# Sheet1.net
KiCad netlist of a schematic drawn in Altium Designer
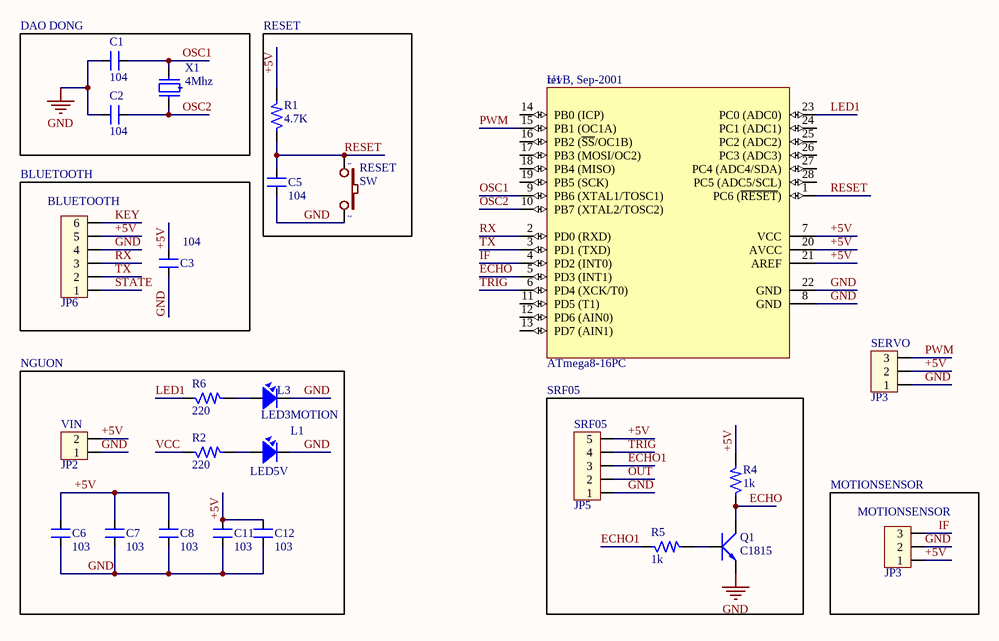
[diagram p0: Sheet1.SchDoc]

(export (version "E")
  (design (tool "Eeschema 10.0.6"))
  (components
    (comp (ref "BLUETOOTH")
      (value "JP6")
      (footprint "CON6")
      (description "Connector 6")
      (libsource (lib "syhaunguyen") (part "Con6"))
    )
    (comp (ref "C1")
      (value "104")
      (footprint "SM-0805")
      (description "Cap SMD")
      (libsource (lib "syhaunguyen") (part "CM"))
    )
    (comp (ref "C2")
      (value "104")
      (footprint "SM-0805")
      (description "Cap SMD")
      (libsource (lib "syhaunguyen") (part "CM"))
    )
    (comp (ref "C3")
      (value "104")
      (footprint "SM-0805")
      (description "Cap SMD")
      (libsource (lib "syhaunguyen") (part "CM"))
    )
    (comp (ref "C5")
      (value "104")
      (footprint "SM-0805")
      (description "Cap SMD")
      (libsource (lib "syhaunguyen") (part "CM"))
    )
    (comp (ref "C6")
      (value "103")
      (footprint "SM-0805")
      (description "Cap SMD")
      (libsource (lib "syhaunguyen") (part "CM"))
    )
    (comp (ref "C7")
      (value "103")
      (footprint "SM-0805")
      (description "Cap SMD")
      (libsource (lib "syhaunguyen") (part "CM"))
    )
    (comp (ref "C8")
      (value "103")
      (footprint "SM-0805")
      (description "Cap SMD")
      (libsource (lib "syhaunguyen") (part "CM"))
    )
    (comp (ref "C11")
      (value "103")
      (footprint "SM-0805")
      (description "Cap SMD")
      (libsource (lib "syhaunguyen") (part "CM"))
    )
    (comp (ref "C12")
      (value "103")
      (footprint "SM-0805")
      (description "Cap SMD")
      (libsource (lib "syhaunguyen") (part "CM"))
    )
    (comp (ref "L1")
      (value "LED5V")
      (footprint "LED-3")
      (description "LED Single colour Green and Red")
      (libsource (lib "syhaunguyen") (part "LED"))
    )
    (comp (ref "L3")
      (value "LED3MOTION")
      (footprint "LED-3")
      (description "LED Single colour Green and Red")
      (libsource (lib "syhaunguyen") (part "LED"))
    )
    (comp (ref "MOTIONSENSOR")
      (value "JP3")
      (footprint "CON3")
      (description "Connector 3")
      (libsource (lib "syhaunguyen") (part "Con3"))
    )
    (comp (ref "Q1")
      (value "C1815")
      (footprint "QTO-92")
      (description "NPN 600mW, ECB")
      (libsource (lib "syhaunguyen") (part "C1815"))
    )
    (comp (ref "R1")
      (value "4.7K")
      (footprint "SM-0805")
      (description "Resistor 1/4W")
      (libsource (lib "syhaunguyen") (part "R"))
    )
    (comp (ref "R2")
      (value "220")
      (footprint "SM-0805")
      (description "Resistor 1/4W")
      (libsource (lib "syhaunguyen") (part "R"))
    )
    (comp (ref "R4")
      (value "1k")
      (footprint "SM-0805")
      (description "Resistor 1/4W")
      (libsource (lib "syhaunguyen") (part "R"))
    )
    (comp (ref "R5")
      (value "1k")
      (footprint "SM-0805")
      (description "Resistor 1/4W")
      (libsource (lib "syhaunguyen") (part "R"))
    )
    (comp (ref "R6")
      (value "220")
      (footprint "SM-0805")
      (description "Resistor 1/4W")
      (libsource (lib "syhaunguyen") (part "R"))
    )
    (comp (ref "RESET")
      (value "SW")
      (footprint "SW2")
      (description "Switch button 2 pin")
      (libsource (lib "syhaunguyen") (part "SW2"))
    )
    (comp (ref "SERVO")
      (value "JP3")
      (footprint "CON3")
      (description "Connector 3")
      (libsource (lib "syhaunguyen") (part "Con3"))
    )
    (comp (ref "SRF05")
      (value "JP5")
      (footprint "CON5")
      (description "Connector 5")
      (libsource (lib "syhaunguyen") (part "Con5"))
    )
    (comp (ref "U1")
      (value "ATmega8-16PC")
      (footprint "28P3")
      (description "8-Bit AVR Microcontroller with 8K Bytes of In-System Programmable Flash Memory")
      (fields (field (name "PACKAGEVERSION") "revB, Sep-2001") (field (name "PUBLISHER") "Altium Limited"))
      (libsource (lib "Atmel Microcontroller 8-Bit AVR") (part "ATmega8-16PC"))
    )
    (comp (ref "VIN")
      (value "JP2")
      (footprint "CON2")
      (description "Connector 2")
      (libsource (lib "syhaunguyen") (part "Con2"))
    )
    (comp (ref "X1")
      (value "4Mhz")
      (footprint "XT2")
      (description "Crystal For all Crystal 2pin.")
      (libsource (lib "syhaunguyen") (part "XT3"))
    )
  )
  (nets
    (net (code "1") (name "/+5V") (class "Default")
      (node (ref "BLUETOOTH") (pin "5") (pinfunction "5_5") (pintype "passive"))
      (node (ref "C11") (pin "2") (pinfunction "2_2") (pintype "passive"))
      (node (ref "C12") (pin "2") (pinfunction "2_2") (pintype "passive"))
      (node (ref "C3") (pin "2") (pinfunction "2_2") (pintype "passive"))
      (node (ref "C6") (pin "2") (pinfunction "2_2") (pintype "passive"))
      (node (ref "C7") (pin "2") (pinfunction "2_2") (pintype "passive"))
      (node (ref "C8") (pin "2") (pinfunction "2_2") (pintype "passive"))
      (node (ref "MOTIONSENSOR") (pin "1") (pinfunction "1_1") (pintype "passive"))
      (node (ref "R1") (pin "2") (pinfunction "2_2") (pintype "passive"))
      (node (ref "R4") (pin "2") (pinfunction "2_2") (pintype "passive"))
      (node (ref "SERVO") (pin "2") (pinfunction "2_2") (pintype "passive"))
      (node (ref "SRF05") (pin "5") (pinfunction "5_5") (pintype "passive"))
      (node (ref "U1") (pin "20") (pinfunction "AVCC_20") (pintype "power_in"))
      (node (ref "U1") (pin "21") (pinfunction "AREF_21") (pintype "passive"))
      (node (ref "U1") (pin "7") (pinfunction "VCC_7") (pintype "power_in"))
      (node (ref "VIN") (pin "2") (pinfunction "2_2") (pintype "passive"))
    )
    (net (code "2") (name "/ECHO") (class "Default")
      (node (ref "Q1") (pin "2") (pinfunction "C_2") (pintype "passive"))
      (node (ref "R4") (pin "1") (pinfunction "1_1") (pintype "passive"))
      (node (ref "U1") (pin "5") (pinfunction "PD3_(INT1)_5") (pintype "bidirectional"))
    )
    (net (code "3") (name "/ECHO1") (class "Default")
      (node (ref "R5") (pin "1") (pinfunction "1_1") (pintype "passive"))
      (node (ref "SRF05") (pin "3") (pinfunction "3_3") (pintype "passive"))
    )
    (net (code "4") (name "/IF") (class "Default")
      (node (ref "MOTIONSENSOR") (pin "3") (pinfunction "3_3") (pintype "passive"))
      (node (ref "U1") (pin "4") (pinfunction "PD2_(INT0)_4") (pintype "bidirectional"))
    )
    (net (code "5") (name "/KEY") (class "Default")
      (node (ref "BLUETOOTH") (pin "6") (pinfunction "6_6") (pintype "passive"))
    )
    (net (code "6") (name "/LED1") (class "Default")
      (node (ref "R6") (pin "1") (pinfunction "1_1") (pintype "passive"))
      (node (ref "U1") (pin "23") (pinfunction "PC0_(ADC0)_23") (pintype "bidirectional"))
    )
    (net (code "7") (name "/OSC1") (class "Default")
      (node (ref "C1") (pin "2") (pinfunction "2_2") (pintype "passive"))
      (node (ref "U1") (pin "9") (pinfunction "PB6_(XTAL1/TOSC1)_9") (pintype "bidirectional"))
      (node (ref "X1") (pin "2") (pinfunction "2_2") (pintype "passive"))
    )
    (net (code "8") (name "/OSC2") (class "Default")
      (node (ref "C2") (pin "2") (pinfunction "2_2") (pintype "passive"))
      (node (ref "U1") (pin "10") (pinfunction "PB7_(XTAL2/TOSC2)_10") (pintype "bidirectional"))
      (node (ref "X1") (pin "1") (pinfunction "1_1") (pintype "passive"))
    )
    (net (code "9") (name "/OUT") (class "Default")
      (node (ref "SRF05") (pin "2") (pinfunction "2_2") (pintype "passive"))
    )
    (net (code "10") (name "/PWM") (class "Default")
      (node (ref "SERVO") (pin "3") (pinfunction "3_3") (pintype "passive"))
      (node (ref "U1") (pin "15") (pinfunction "PB1_(OC1A)_15") (pintype "bidirectional"))
    )
    (net (code "11") (name "/RESET") (class "Default")
      (node (ref "C5") (pin "2") (pinfunction "2_2") (pintype "passive"))
      (node (ref "R1") (pin "1") (pinfunction "1_1") (pintype "passive"))
      (node (ref "RESET") (pin "1") (pinfunction "1_1") (pintype "passive"))
      (node (ref "U1") (pin "1") (pinfunction "PC6_(~{RESET})_1") (pintype "bidirectional"))
    )
    (net (code "12") (name "/RX") (class "Default")
      (node (ref "BLUETOOTH") (pin "3") (pinfunction "3_3") (pintype "passive"))
      (node (ref "U1") (pin "2") (pinfunction "PD0_(RXD)_2") (pintype "bidirectional"))
    )
    (net (code "13") (name "/STATE") (class "Default")
      (node (ref "BLUETOOTH") (pin "1") (pinfunction "1_1") (pintype "passive"))
    )
    (net (code "14") (name "/TRIG") (class "Default")
      (node (ref "SRF05") (pin "4") (pinfunction "4_4") (pintype "passive"))
      (node (ref "U1") (pin "6") (pinfunction "PD4_(XCK/T0)_6") (pintype "bidirectional"))
    )
    (net (code "15") (name "/TX") (class "Default")
      (node (ref "BLUETOOTH") (pin "2") (pinfunction "2_2") (pintype "passive"))
      (node (ref "U1") (pin "3") (pinfunction "PD1_(TXD)_3") (pintype "bidirectional"))
    )
    (net (code "16") (name "/VCC") (class "Default")
      (node (ref "R2") (pin "1") (pinfunction "1_1") (pintype "passive"))
    )
    (net (code "17") (name "GND") (class "Default")
      (node (ref "BLUETOOTH") (pin "4") (pinfunction "4_4") (pintype "passive"))
      (node (ref "C1") (pin "1") (pinfunction "1_1") (pintype "passive"))
      (node (ref "C11") (pin "1") (pinfunction "1_1") (pintype "passive"))
      (node (ref "C12") (pin "1") (pinfunction "1_1") (pintype "passive"))
      (node (ref "C2") (pin "1") (pinfunction "1_1") (pintype "passive"))
      (node (ref "C3") (pin "1") (pinfunction "1_1") (pintype "passive"))
      (node (ref "C5") (pin "1") (pinfunction "1_1") (pintype "passive"))
      (node (ref "C6") (pin "1") (pinfunction "1_1") (pintype "passive"))
      (node (ref "C7") (pin "1") (pinfunction "1_1") (pintype "passive"))
      (node (ref "C8") (pin "1") (pinfunction "1_1") (pintype "passive"))
      (node (ref "L1") (pin "2") (pinfunction "2_2") (pintype "passive"))
      (node (ref "L3") (pin "2") (pinfunction "2_2") (pintype "passive"))
      (node (ref "MOTIONSENSOR") (pin "2") (pinfunction "2_2") (pintype "passive"))
      (node (ref "Q1") (pin "1") (pinfunction "E_1") (pintype "passive"))
      (node (ref "RESET") (pin "2") (pinfunction "2_2") (pintype "passive"))
      (node (ref "SERVO") (pin "1") (pinfunction "1_1") (pintype "passive"))
      (node (ref "SRF05") (pin "1") (pinfunction "1_1") (pintype "passive"))
      (node (ref "U1") (pin "22") (pinfunction "GND_22") (pintype "power_in"))
      (node (ref "U1") (pin "8") (pinfunction "GND_8") (pintype "power_in"))
      (node (ref "VIN") (pin "1") (pinfunction "1_1") (pintype "passive"))
    )
    (net (code "18") (name "Net-(L1-Pad1)") (class "Default")
      (node (ref "L1") (pin "1") (pinfunction "1_1") (pintype "passive"))
      (node (ref "R2") (pin "2") (pinfunction "2_2") (pintype "passive"))
    )
    (net (code "19") (name "Net-(L3-Pad1)") (class "Default")
      (node (ref "L3") (pin "1") (pinfunction "1_1") (pintype "passive"))
      (node (ref "R6") (pin "2") (pinfunction "2_2") (pintype "passive"))
    )
    (net (code "20") (name "Net-(Q1-B)") (class "Default")
      (node (ref "Q1") (pin "3") (pinfunction "B_3") (pintype "passive"))
      (node (ref "R5") (pin "2") (pinfunction "2_2") (pintype "passive"))
    )
    (net (code "21") (name "unconnected-(U1-PB0_(ICP)-Pad14)") (class "Default")
      (node (ref "U1") (pin "14") (pinfunction "PB0_(ICP)_14") (pintype "bidirectional"))
    )
    (net (code "22") (name "unconnected-(U1-PB2_(~{SS}{slash}OC1B)-Pad16)") (class "Default")
      (node (ref "U1") (pin "16") (pinfunction "PB2_(~{SS}/OC1B)_16") (pintype "bidirectional"))
    )
    (net (code "23") (name "unconnected-(U1-PB3_(MOSI{slash}OC2)-Pad17)") (class "Default")
      (node (ref "U1") (pin "17") (pinfunction "PB3_(MOSI/OC2)_17") (pintype "bidirectional"))
    )
    (net (code "24") (name "unconnected-(U1-PB4_(MISO)-Pad18)") (class "Default")
      (node (ref "U1") (pin "18") (pinfunction "PB4_(MISO)_18") (pintype "bidirectional"))
    )
    (net (code "25") (name "unconnected-(U1-PB5_(SCK)-Pad19)") (class "Default")
      (node (ref "U1") (pin "19") (pinfunction "PB5_(SCK)_19") (pintype "bidirectional"))
    )
    (net (code "26") (name "unconnected-(U1-PC1_(ADC1)-Pad24)") (class "Default")
      (node (ref "U1") (pin "24") (pinfunction "PC1_(ADC1)_24") (pintype "bidirectional"))
    )
    (net (code "27") (name "unconnected-(U1-PC2_(ADC2)-Pad25)") (class "Default")
      (node (ref "U1") (pin "25") (pinfunction "PC2_(ADC2)_25") (pintype "bidirectional"))
    )
    (net (code "28") (name "unconnected-(U1-PC3_(ADC3)-Pad26)") (class "Default")
      (node (ref "U1") (pin "26") (pinfunction "PC3_(ADC3)_26") (pintype "bidirectional"))
    )
    (net (code "29") (name "unconnected-(U1-PC4_(ADC4{slash}SDA)-Pad27)") (class "Default")
      (node (ref "U1") (pin "27") (pinfunction "PC4_(ADC4/SDA)_27") (pintype "bidirectional"))
    )
    (net (code "30") (name "unconnected-(U1-PC5_(ADC5{slash}SCL)-Pad28)") (class "Default")
      (node (ref "U1") (pin "28") (pinfunction "PC5_(ADC5/SCL)_28") (pintype "bidirectional"))
    )
    (net (code "31") (name "unconnected-(U1-PD5_(T1)-Pad11)") (class "Default")
      (node (ref "U1") (pin "11") (pinfunction "PD5_(T1)_11") (pintype "bidirectional"))
    )
    (net (code "32") (name "unconnected-(U1-PD6_(AIN0)-Pad12)") (class "Default")
      (node (ref "U1") (pin "12") (pinfunction "PD6_(AIN0)_12") (pintype "bidirectional"))
    )
    (net (code "33") (name "unconnected-(U1-PD7_(AIN1)-Pad13)") (class "Default")
      (node (ref "U1") (pin "13") (pinfunction "PD7_(AIN1)_13") (pintype "bidirectional"))
    )
    (net (code "34") (name "unconnected-(X1-Pad3)") (class "Default")
      (node (ref "X1") (pin "3") (pinfunction "3_3") (pintype "passive"))
    )
  )
)
